# 74HC595.net
KiCad netlist of a schematic drawn in Altium Designer
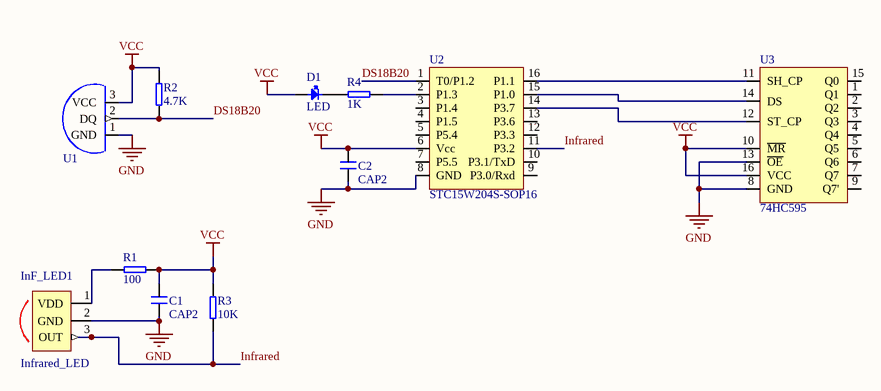
[diagram p0: 74HC595.SchDoc]

(export (version "E")
  (design (tool "Eeschema 10.0.6"))
  (components
    (comp (ref "C1") (value "CAP2") (footprint "0805") (libsource (lib "MaWei") (part "CAP2")))
    (comp (ref "C2") (value "CAP2") (footprint "0805") (libsource (lib "MaWei") (part "CAP2")))
    (comp (ref "D1") (value "LED") (footprint "LED0805") (libsource (lib "MaWei") (part "LED")))
    (comp (ref "InF_LED1")
      (value "Infrared_LED")
      (footprint "IR")
      (libsource (lib "MaWei") (part "Infrared_LED"))
    )
    (comp (ref "R1") (value "100") (footprint "RES0805") (libsource (lib "MaWei") (part "RES")))
    (comp (ref "R2") (value "4.7K") (footprint "RES0805") (libsource (lib "MaWei") (part "RES")))
    (comp (ref "R3") (value "10K") (footprint "RES0805") (libsource (lib "MaWei") (part "RES")))
    (comp (ref "R4") (value "1K") (footprint "RES0805") (libsource (lib "MaWei") (part "RES")))
    (comp (ref "U1") (value "DS18B20") (footprint "3PIN") (libsource (lib "MaWei") (part "DS18B20")))
    (comp (ref "U2")
      (value "STC15W204S-SOP16")
      (footprint "SOP16")
      (libsource (lib "MaWei") (part "STC15W204S-SOP16"))
    )
    (comp (ref "U3") (value "74HC595") (footprint "SOP16") (libsource (lib "MaWei") (part "74HC595")))
  )
  (nets
    (net (code "1") (name "/DS18B20") (class "Default")
      (node (ref "R2") (pin "1") (pinfunction "1_1") (pintype "passive"))
      (node (ref "U1") (pin "2") (pinfunction "DQ_2") (pintype "output"))
      (node (ref "U2") (pin "1") (pinfunction "T0/P1.2_1") (pintype "passive"))
    )
    (net (code "2") (name "/Infrared") (class "Default")
      (node (ref "InF_LED1") (pin "3") (pinfunction "OUT_3") (pintype "output"))
      (node (ref "R3") (pin "1") (pinfunction "1_1") (pintype "passive"))
      (node (ref "U2") (pin "11") (pinfunction "P3.2_11") (pintype "passive"))
    )
    (net (code "3") (name "GND") (class "Default")
      (node (ref "C1") (pin "1") (pintype "passive"))
      (node (ref "C2") (pin "1") (pintype "passive"))
      (node (ref "InF_LED1") (pin "2") (pinfunction "GND_2") (pintype "passive"))
      (node (ref "U1") (pin "1") (pinfunction "GND_1") (pintype "passive"))
      (node (ref "U2") (pin "8") (pinfunction "GND_8") (pintype "passive"))
      (node (ref "U3") (pin "13") (pinfunction "~{OE}_13") (pintype "passive"))
      (node (ref "U3") (pin "8") (pinfunction "GND_8") (pintype "passive"))
    )
    (net (code "4") (name "Net-(D1-K)") (class "Default")
      (node (ref "D1") (pin "2") (pinfunction "K_2") (pintype "passive"))
      (node (ref "R4") (pin "2") (pinfunction "2_2") (pintype "passive"))
    )
    (net (code "5") (name "Net-(InF_LED1-VDD)") (class "Default")
      (node (ref "InF_LED1") (pin "1") (pinfunction "VDD_1") (pintype "passive"))
      (node (ref "R1") (pin "1") (pinfunction "1_1") (pintype "passive"))
    )
    (net (code "6") (name "Net-(U2-P1.0)") (class "Default")
      (node (ref "U2") (pin "15") (pinfunction "P1.0_15") (pintype "passive"))
      (node (ref "U3") (pin "14") (pinfunction "DS_14") (pintype "passive"))
    )
    (net (code "7") (name "Net-(U2-P1.1)") (class "Default")
      (node (ref "U2") (pin "16") (pinfunction "P1.1_16") (pintype "passive"))
      (node (ref "U3") (pin "11") (pinfunction "SH_CP_11") (pintype "passive"))
    )
    (net (code "8") (name "Net-(U2-P1.3)") (class "Default")
      (node (ref "R4") (pin "1") (pinfunction "1_1") (pintype "passive"))
      (node (ref "U2") (pin "2") (pinfunction "P1.3_2") (pintype "passive"))
    )
    (net (code "9") (name "Net-(U2-P3.7)") (class "Default")
      (node (ref "U2") (pin "14") (pinfunction "P3.7_14") (pintype "passive"))
      (node (ref "U3") (pin "12") (pinfunction "ST_CP_12") (pintype "passive"))
    )
    (net (code "10") (name "VCC") (class "Default")
      (node (ref "C1") (pin "2") (pintype "passive"))
      (node (ref "C2") (pin "2") (pintype "passive"))
      (node (ref "D1") (pin "1") (pinfunction "A_1") (pintype "passive"))
      (node (ref "R1") (pin "2") (pinfunction "2_2") (pintype "passive"))
      (node (ref "R2") (pin "2") (pinfunction "2_2") (pintype "passive"))
      (node (ref "R3") (pin "2") (pinfunction "2_2") (pintype "passive"))
      (node (ref "U1") (pin "3") (pinfunction "VCC_3") (pintype "passive"))
      (node (ref "U2") (pin "6") (pinfunction "Vcc_6") (pintype "passive"))
      (node (ref "U3") (pin "10") (pinfunction "~{MR}_10") (pintype "passive"))
      (node (ref "U3") (pin "16") (pinfunction "VCC_16") (pintype "passive"))
    )
    (net (code "11") (name "unconnected-(U2-P1.4-Pad3)") (class "Default")
      (node (ref "U2") (pin "3") (pinfunction "P1.4_3") (pintype "passive"))
    )
    (net (code "12") (name "unconnected-(U2-P1.5-Pad4)") (class "Default")
      (node (ref "U2") (pin "4") (pinfunction "P1.5_4") (pintype "passive"))
    )
    (net (code "13") (name "unconnected-(U2-P3.0{slash}Rxd-Pad9)") (class "Default")
      (node (ref "U2") (pin "9") (pinfunction "P3.0/Rxd_9") (pintype "passive"))
    )
    (net (code "14") (name "unconnected-(U2-P3.1{slash}TxD-Pad10)") (class "Default")
      (node (ref "U2") (pin "10") (pinfunction "P3.1/TxD_10") (pintype "passive"))
    )
    (net (code "15") (name "unconnected-(U2-P3.3-Pad12)") (class "Default")
      (node (ref "U2") (pin "12") (pinfunction "P3.3_12") (pintype "passive"))
    )
    (net (code "16") (name "unconnected-(U2-P3.6-Pad13)") (class "Default")
      (node (ref "U2") (pin "13") (pinfunction "P3.6_13") (pintype "passive"))
    )
    (net (code "17") (name "unconnected-(U2-P5.4-Pad5)") (class "Default")
      (node (ref "U2") (pin "5") (pinfunction "P5.4_5") (pintype "passive"))
    )
    (net (code "18") (name "unconnected-(U2-P5.5-Pad7)") (class "Default")
      (node (ref "U2") (pin "7") (pinfunction "P5.5_7") (pintype "passive"))
    )
    (net (code "19") (name "unconnected-(U3-Q0-Pad15)") (class "Default")
      (node (ref "U3") (pin "15") (pinfunction "Q0_15") (pintype "passive"))
    )
    (net (code "20") (name "unconnected-(U3-Q1-Pad1)") (class "Default")
      (node (ref "U3") (pin "1") (pinfunction "Q1_1") (pintype "passive"))
    )
    (net (code "21") (name "unconnected-(U3-Q2-Pad2)") (class "Default")
      (node (ref "U3") (pin "2") (pinfunction "Q2_2") (pintype "passive"))
    )
    (net (code "22") (name "unconnected-(U3-Q3-Pad3)") (class "Default")
      (node (ref "U3") (pin "3") (pinfunction "Q3_3") (pintype "passive"))
    )
    (net (code "23") (name "unconnected-(U3-Q4-Pad4)") (class "Default")
      (node (ref "U3") (pin "4") (pinfunction "Q4_4") (pintype "passive"))
    )
    (net (code "24") (name "unconnected-(U3-Q5-Pad5)") (class "Default")
      (node (ref "U3") (pin "5") (pinfunction "Q5_5") (pintype "passive"))
    )
    (net (code "25") (name "unconnected-(U3-Q6-Pad6)") (class "Default")
      (node (ref "U3") (pin "6") (pinfunction "Q6_6") (pintype "passive"))
    )
    (net (code "26") (name "unconnected-(U3-Q7'-Pad9)") (class "Default")
      (node (ref "U3") (pin "9") (pinfunction "Q7'_9") (pintype "passive"))
    )
    (net (code "27") (name "unconnected-(U3-Q7-Pad7)") (class "Default")
      (node (ref "U3") (pin "7") (pinfunction "Q7_7") (pintype "passive"))
    )
  )
)
